# sch.net
KiCad netlist of a schematic drawn in Altium Designer
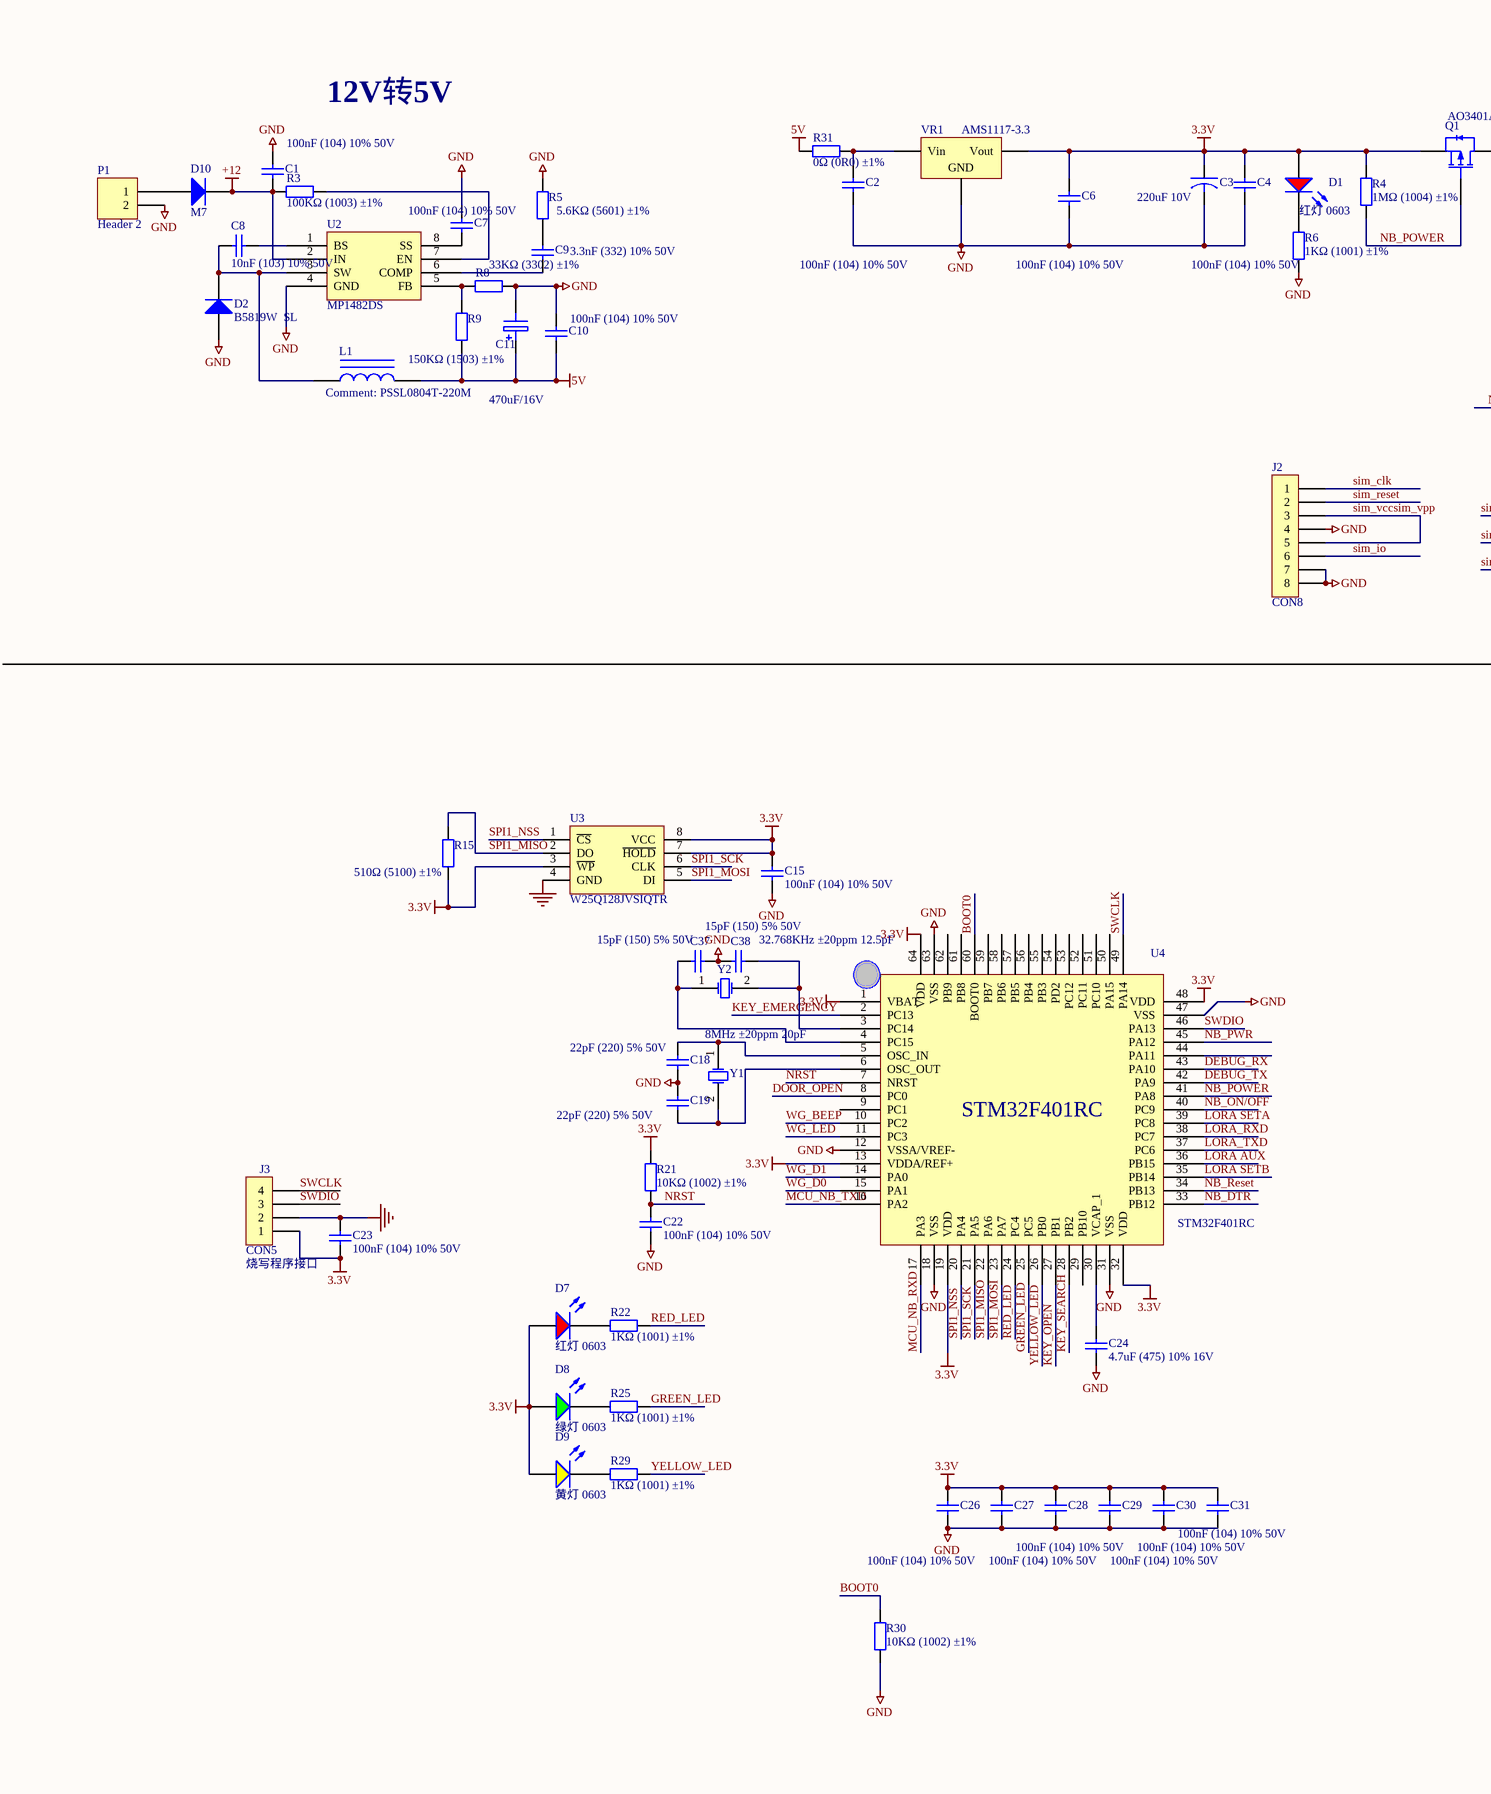
[diagram p0: sch.SchDoc, left]
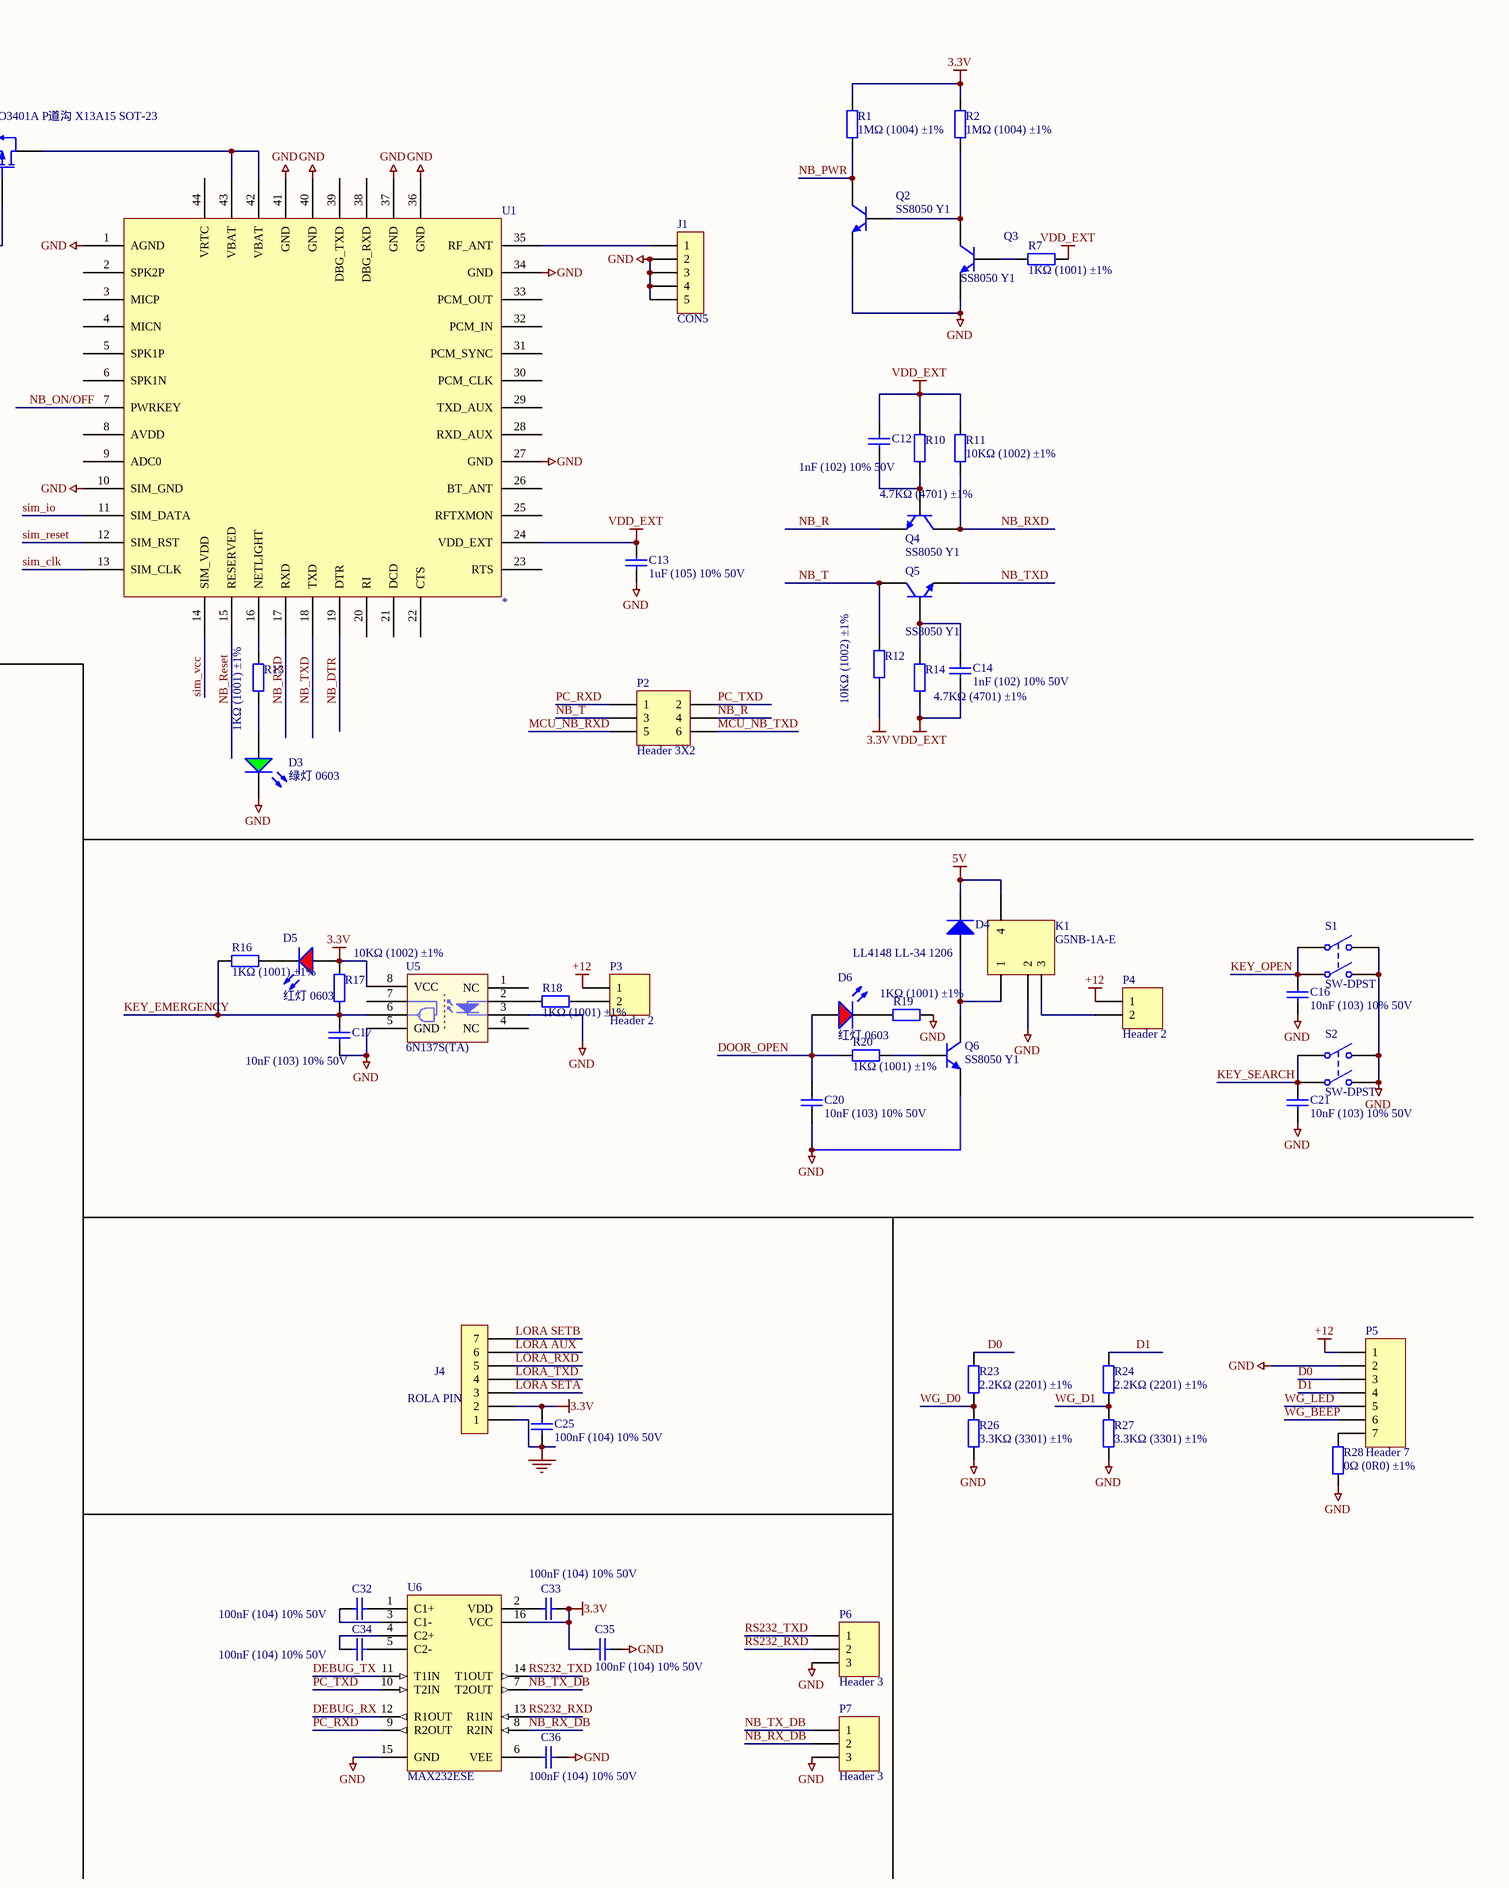
[diagram p1: sch.SchDoc, right]

(export (version "E")
  (design (tool "Eeschema 10.0.6"))
  (components
    (comp (ref "C1")
      (value "100nF (104) 10% 50V")
      (footprint "0603_C")
      (description "贴片电容")
      (libsource (lib "Cap") (part "0603 100nF (104) 10% 50V"))
    )
    (comp (ref "C2")
      (value "100nF (104) 10% 50V")
      (footprint "0603_C")
      (description "贴片电容")
      (libsource (lib "Cap") (part "0603 100nF (104) 10% 50V"))
    )
    (comp (ref "C3")
      (value "220uF 10V")
      (footprint "153CLV-0807")
      (description "Capacitor")
      (libsource (lib "*") (part "CAPACITOR"))
    )
    (comp (ref "C4")
      (value "100nF (104) 10% 50V")
      (footprint "0603_C")
      (description "贴片电容")
      (libsource (lib "Cap") (part "0603 100nF (104) 10% 50V"))
    )
    (comp (ref "C6")
      (value "100nF (104) 10% 50V")
      (footprint "0603_C")
      (description "贴片电容")
      (libsource (lib "Cap") (part "0603 100nF (104) 10% 50V"))
    )
    (comp (ref "C7")
      (value "100nF (104) 10% 50V")
      (footprint "0603_C")
      (description "贴片电容")
      (libsource (lib "Cap") (part "0603 100nF (104) 10% 50V"))
    )
    (comp (ref "C8")
      (value "10nF (103) 10% 50V")
      (footprint "0603_C")
      (description "贴片电容")
      (libsource (lib "Cap") (part "0603 10nF (103) 10% 50V"))
    )
    (comp (ref "C9")
      (value "3.3nF (332) 10% 50V")
      (footprint "0603_C")
      (description "贴片电容")
      (libsource (lib "Cap") (part "0603 3.3nF (332) 10% 50V"))
    )
    (comp (ref "C10")
      (value "100nF (104) 10% 50V")
      (footprint "0603_C")
      (description "贴片电容")
      (libsource (lib "Cap") (part "0603 100nF (104) 10% 50V"))
    )
    (comp (ref "C11")
      (value "470uF/16V")
      (footprint "153CLV-0810")
      (description "Electrolytic Capacitor")
      (libsource (lib "*") (part "ELECTRO1"))
    )
    (comp (ref "C12")
      (value "1nF (102) 10% 50V")
      (footprint "0603_C")
      (description "贴片电容")
      (libsource (lib "Cap") (part "0603 1nF (102) 10% 50V"))
    )
    (comp (ref "C13")
      (value "1uF (105) 10% 50V")
      (footprint "0603_C")
      (description "贴片电容")
      (libsource (lib "Cap") (part "0603 1uF (105) 10% 50V"))
    )
    (comp (ref "C14")
      (value "1nF (102) 10% 50V")
      (footprint "0603_C")
      (description "贴片电容")
      (libsource (lib "Cap") (part "0603 1nF (102) 10% 50V"))
    )
    (comp (ref "C15")
      (value "100nF (104) 10% 50V")
      (footprint "0603_C")
      (description "贴片电容")
      (libsource (lib "Cap") (part "0603 100nF (104) 10% 50V"))
    )
    (comp (ref "C16")
      (value "10nF (103) 10% 50V")
      (footprint "0603_C")
      (description "贴片电容")
      (libsource (lib "Cap") (part "0603 10nF (103) 10% 50V"))
    )
    (comp (ref "C17")
      (value "10nF (103) 10% 50V")
      (footprint "0603_C")
      (description "贴片电容")
      (libsource (lib "Cap") (part "0603 10nF (103) 10% 50V"))
    )
    (comp (ref "C18")
      (value "22pF (220) 5% 50V")
      (footprint "0603_C")
      (description "贴片电容")
      (libsource (lib "Cap") (part "0603 22pF (220) 5% 50V"))
    )
    (comp (ref "C19")
      (value "22pF (220) 5% 50V")
      (footprint "0603_C")
      (description "贴片电容")
      (libsource (lib "Cap") (part "0603 22pF (220) 5% 50V"))
    )
    (comp (ref "C20")
      (value "10nF (103) 10% 50V")
      (footprint "0603_C")
      (description "贴片电容")
      (libsource (lib "Cap") (part "0603 10nF (103) 10% 50V"))
    )
    (comp (ref "C21")
      (value "10nF (103) 10% 50V")
      (footprint "0603_C")
      (description "贴片电容")
      (libsource (lib "Cap") (part "0603 10nF (103) 10% 50V"))
    )
    (comp (ref "C22")
      (value "100nF (104) 10% 50V")
      (footprint "0603_C")
      (description "贴片电容")
      (libsource (lib "Cap") (part "0603 100nF (104) 10% 50V"))
    )
    (comp (ref "C23")
      (value "100nF (104) 10% 50V")
      (footprint "0603_C")
      (description "贴片电容")
      (libsource (lib "Cap") (part "0603 100nF (104) 10% 50V"))
    )
    (comp (ref "C24")
      (value "4.7uF (475) 10% 16V")
      (footprint "0603_C")
      (description "贴片电容")
      (libsource (lib "Cap") (part "0603 4.7uF (475) 10% 16V"))
    )
    (comp (ref "C25")
      (value "100nF (104) 10% 50V")
      (footprint "0603_C")
      (description "贴片电容")
      (libsource (lib "Cap") (part "0603 100nF (104) 10% 50V"))
    )
    (comp (ref "C26")
      (value "100nF (104) 10% 50V")
      (footprint "0603_C")
      (description "贴片电容")
      (libsource (lib "Cap") (part "0603 100nF (104) 10% 50V"))
    )
    (comp (ref "C27")
      (value "100nF (104) 10% 50V")
      (footprint "0603_C")
      (description "贴片电容")
      (libsource (lib "Cap") (part "0603 100nF (104) 10% 50V"))
    )
    (comp (ref "C28")
      (value "100nF (104) 10% 50V")
      (footprint "0603_C")
      (description "贴片电容")
      (libsource (lib "Cap") (part "0603 100nF (104) 10% 50V"))
    )
    (comp (ref "C29")
      (value "100nF (104) 10% 50V")
      (footprint "0603_C")
      (description "贴片电容")
      (libsource (lib "Cap") (part "0603 100nF (104) 10% 50V"))
    )
    (comp (ref "C30")
      (value "100nF (104) 10% 50V")
      (footprint "0603_C")
      (description "贴片电容")
      (libsource (lib "Cap") (part "0603 100nF (104) 10% 50V"))
    )
    (comp (ref "C31")
      (value "100nF (104) 10% 50V")
      (footprint "0603_C")
      (description "贴片电容")
      (libsource (lib "Cap") (part "0603 100nF (104) 10% 50V"))
    )
    (comp (ref "C32")
      (value "100nF (104) 10% 50V")
      (footprint "0603_C")
      (description "贴片电容")
      (libsource (lib "Cap") (part "0603 100nF (104) 10% 50V"))
    )
    (comp (ref "C33")
      (value "100nF (104) 10% 50V")
      (footprint "0603_C")
      (description "贴片电容")
      (libsource (lib "Cap") (part "0603 100nF (104) 10% 50V"))
    )
    (comp (ref "C34")
      (value "100nF (104) 10% 50V")
      (footprint "0603_C")
      (description "贴片电容")
      (libsource (lib "Cap") (part "0603 100nF (104) 10% 50V"))
    )
    (comp (ref "C35")
      (value "100nF (104) 10% 50V")
      (footprint "0603_C")
      (description "贴片电容")
      (libsource (lib "Cap") (part "0603 100nF (104) 10% 50V"))
    )
    (comp (ref "C36")
      (value "100nF (104) 10% 50V")
      (footprint "0603_C")
      (description "贴片电容")
      (libsource (lib "Cap") (part "0603 100nF (104) 10% 50V"))
    )
    (comp (ref "C37")
      (value "15pF (150) 5% 50V")
      (footprint "0603_C")
      (description "贴片电容")
      (libsource (lib "Cap") (part "0603 15pF (150) 5% 50V"))
    )
    (comp (ref "C38")
      (value "15pF (150) 5% 50V")
      (footprint "0603_C")
      (description "贴片电容")
      (libsource (lib "Cap") (part "0603 15pF (150) 5% 50V"))
    )
    (comp (ref "D1")
      (value "红灯 0603")
      (footprint "0603_LED_S1")
      (description "发光二极管")
      (libsource (lib "LED") (part "0603 红灯"))
    )
    (comp (ref "D2")
      (value "B5819W  SL")
      (footprint "SOD-123")
      (description "肖特基二极管")
      (libsource (lib "Diode") (part "SOD-123 B5819W  SL"))
    )
    (comp (ref "D3")
      (value "绿灯 0603")
      (footprint "0603_LED_S1")
      (description "发光二极管")
      (libsource (lib "LED") (part "0603 绿灯"))
    )
    (comp (ref "D4")
      (value "LL4148 LL-34 1206")
      (footprint "LL-34")
      (description "开关二极管")
      (libsource (lib "Diode") (part "LL-34 LL4148 LL-34 1206"))
    )
    (comp (ref "D5")
      (value "红灯 0603")
      (footprint "0603_LED_S1")
      (description "发光二极管")
      (libsource (lib "LED") (part "0603 红灯"))
    )
    (comp (ref "D6")
      (value "红灯 0603")
      (footprint "0603_LED_S1")
      (description "发光二极管")
      (libsource (lib "LED") (part "0603 红灯"))
    )
    (comp (ref "D7")
      (value "红灯 0603")
      (footprint "0603_LED_S1")
      (description "发光二极管")
      (libsource (lib "LED") (part "0603 红灯"))
    )
    (comp (ref "D8")
      (value "绿灯 0603")
      (footprint "0603_LED_S1")
      (description "发光二极管")
      (libsource (lib "LED") (part "0603 绿灯"))
    )
    (comp (ref "D9")
      (value "黄灯 0603")
      (footprint "0603_LED_S1")
      (description "发光二极管")
      (libsource (lib "LED") (part "0603 黄灯"))
    )
    (comp (ref "D10")
      (value "M7")
      (footprint "SMA(DO-214AC)_S1")
      (description "二极管")
      (libsource (lib "Diode") (part "SMA(DO-214AC) M7"))
    )
    (comp (ref "J1")
      (value "CON5")
      (footprint "T-5P")
      (description "Connector")
      (libsource (lib "*") (part "CON5"))
    )
    (comp (ref "J2")
      (value "CON8")
      (footprint "NANOSIM")
      (description "Connector")
      (libsource (lib "*") (part "CON8"))
    )
    (comp (ref "J3")
      (value "CON5")
      (footprint "SIP4")
      (description "Connector")
      (libsource (lib "*") (part "CON4"))
    )
    (comp (ref "J4")
      (value "ROLA PIN")
      (footprint "ROLA MODULE")
      (description "Connector")
      (libsource (lib "*") (part "CON7"))
    )
    (comp (ref "K1") (value "G5NB-1A-E") (footprint "G5NB-1A") (libsource (lib "*") (part "G5NB-1A-E")))
    (comp (ref "L1") (value "PSSL0804T-220M") (footprint "L7-8") (libsource (lib "*") (part "INDUCTOR IRON")))
    (comp (ref "P1")
      (value "Header 2")
      (footprint "MSTBV2")
      (description "Header, 2-Pin")
      (fields (field (name "PUBLISHER") "Altium Limited"))
      (libsource (lib "Miscellaneous Connectors") (part "Header 2"))
    )
    (comp (ref "P2")
      (value "Header 3X2")
      (footprint "HDR2X3")
      (description "Header, 3-Pin, Dual row")
      (fields (field (name "PUBLISHER") "Altium Limited"))
      (libsource (lib "Miscellaneous Connectors") (part "Header 3X2"))
    )
    (comp (ref "P3")
      (value "Header 2")
      (footprint "MSTBV2")
      (description "Header, 2-Pin")
      (fields (field (name "PUBLISHER") "Altium Limited"))
      (libsource (lib "") (part "Header 2_1"))
    )
    (comp (ref "P4")
      (value "Header 2")
      (footprint "MSTBV2")
      (description "Header, 2-Pin")
      (fields (field (name "PUBLISHER") "Altium Limited"))
      (libsource (lib "") (part "Header 2_1"))
    )
    (comp (ref "P5")
      (value "Header 7")
      (footprint "MSTBV7")
      (description "Header, 7-Pin")
      (fields (field (name "PUBLISHER") "Altium Limited"))
      (libsource (lib "Miscellaneous Connectors") (part "Header 7"))
    )
    (comp (ref "P6")
      (value "Header 3")
      (footprint "HDR1X3")
      (description "Header, 3-Pin")
      (fields (field (name "PUBLISHER") "Altium Limited"))
      (libsource (lib "Miscellaneous Connectors") (part "Header 3"))
    )
    (comp (ref "P7")
      (value "Header 3")
      (footprint "HDR1X3")
      (description "Header, 3-Pin")
      (fields (field (name "PUBLISHER") "Altium Limited"))
      (libsource (lib "Miscellaneous Connectors") (part "Header 3"))
    )
    (comp (ref "Q1")
      (value "AO3401A P道沟 X13A15 SOT-23")
      (footprint "SOT-23-3L")
      (description "MOS(场效应管)")
      (libsource (lib "MOS") (part "AO3401A P道沟 X13A15 SOT-23"))
    )
    (comp (ref "Q2")
      (value "SS8050 Y1")
      (footprint "SOT-23(SOT-23-3)")
      (description "三极管")
      (libsource (lib "Transistor_NPN") (part "SOT-23 SS8050 Y1"))
    )
    (comp (ref "Q3")
      (value "SS8050 Y1")
      (footprint "SOT-23(SOT-23-3)")
      (description "三极管")
      (libsource (lib "Transistor_NPN") (part "SOT-23 SS8050 Y1"))
    )
    (comp (ref "Q4")
      (value "SS8050 Y1")
      (footprint "SOT-23(SOT-23-3)")
      (description "三极管")
      (libsource (lib "Transistor_NPN") (part "SOT-23 SS8050 Y1"))
    )
    (comp (ref "Q5")
      (value "SS8050 Y1")
      (footprint "SOT-23(SOT-23-3)")
      (description "三极管")
      (libsource (lib "Transistor_NPN") (part "SOT-23 SS8050 Y1"))
    )
    (comp (ref "Q6")
      (value "SS8050 Y1")
      (footprint "SOT-23(SOT-23-3)")
      (description "三极管")
      (libsource (lib "Transistor_NPN") (part "SOT-23 SS8050 Y1"))
    )
    (comp (ref "R1")
      (value "1MΩ (1004) ±1%")
      (footprint "0603_R")
      (description "贴片电阻")
      (libsource (lib "RES") (part "0603 1MΩ (1004) 1%"))
    )
    (comp (ref "R2")
      (value "1MΩ (1004) ±1%")
      (footprint "0603_R")
      (description "贴片电阻")
      (libsource (lib "RES") (part "0603 1MΩ (1004) 1%"))
    )
    (comp (ref "R3")
      (value "100KΩ (1003) ±1%")
      (footprint "0603_R")
      (description "贴片电阻")
      (libsource (lib "RES") (part "0603 100KΩ (1003) 1%"))
    )
    (comp (ref "R4")
      (value "1MΩ (1004) ±1%")
      (footprint "0603_R")
      (description "贴片电阻")
      (libsource (lib "RES") (part "0603 1MΩ (1004) 1%"))
    )
    (comp (ref "R5")
      (value "5.6KΩ (5601) ±1%")
      (footprint "0603_R")
      (description "贴片电阻")
      (libsource (lib "RES") (part "0603 5.6KΩ (5601) 1%"))
    )
    (comp (ref "R6")
      (value "1KΩ (1001) ±1%")
      (footprint "0603_R")
      (description "贴片电阻")
      (libsource (lib "RES") (part "0603 1KΩ (1001) 1%"))
    )
    (comp (ref "R7")
      (value "1KΩ (1001) ±1%")
      (footprint "0603_R")
      (description "贴片电阻")
      (libsource (lib "") (part "0603 1KΩ (1001) 1%_1"))
    )
    (comp (ref "R8")
      (value "33KΩ (3302) ±1%")
      (footprint "0603_R")
      (description "贴片电阻")
      (libsource (lib "RES") (part "0603 33KΩ (3302) 1%"))
    )
    (comp (ref "R9")
      (value "150KΩ (1503) ±1%")
      (footprint "0603_R")
      (description "贴片电阻")
      (libsource (lib "RES") (part "0603 150KΩ (1503) 1%"))
    )
    (comp (ref "R10")
      (value "4.7KΩ (4701) ±1%")
      (footprint "0603_R")
      (description "贴片电阻")
      (libsource (lib "RES") (part "0603 4.7KΩ (4701) 1%"))
    )
    (comp (ref "R11")
      (value "10KΩ (1002) ±1%")
      (footprint "0603_R")
      (description "贴片电阻")
      (libsource (lib "RES") (part "0603 10KΩ (1002) 1%"))
    )
    (comp (ref "R12")
      (value "10KΩ (1002) ±1%")
      (footprint "0603_R")
      (description "贴片电阻")
      (libsource (lib "RES") (part "0603 10KΩ (1002) 1%"))
    )
    (comp (ref "R13")
      (value "1KΩ (1001) ±1%")
      (footprint "0603_R")
      (description "贴片电阻")
      (libsource (lib "RES") (part "0603 1KΩ (1001) 1%"))
    )
    (comp (ref "R14")
      (value "4.7KΩ (4701) ±1%")
      (footprint "0603_R")
      (description "贴片电阻")
      (libsource (lib "RES") (part "0603 4.7KΩ (4701) 1%"))
    )
    (comp (ref "R15")
      (value "510Ω (5100) ±1%")
      (footprint "0603_R")
      (description "贴片电阻")
      (libsource (lib "RES") (part "0603 510Ω (5100) 1%"))
    )
    (comp (ref "R16")
      (value "1KΩ (1001) ±1%")
      (footprint "0603_R")
      (description "贴片电阻")
      (libsource (lib "") (part "0603 1KΩ (1001) 1%_1"))
    )
    (comp (ref "R17")
      (value "10KΩ (1002) ±1%")
      (footprint "0603_R")
      (description "贴片电阻")
      (libsource (lib "") (part "0603 10KΩ (1002) 1%_1"))
    )
    (comp (ref "R18")
      (value "1KΩ (1001) ±1%")
      (footprint "1206_R")
      (description "贴片电阻")
      (libsource (lib "RES") (part "1206 1KΩ (1001) 1%"))
    )
    (comp (ref "R19")
      (value "1KΩ (1001) ±1%")
      (footprint "0603_R")
      (description "贴片电阻")
      (libsource (lib "") (part "0603 1KΩ (1001) 1%_2"))
    )
    (comp (ref "R20")
      (value "1KΩ (1001) ±1%")
      (footprint "0603_R")
      (description "贴片电阻")
      (libsource (lib "") (part "0603 1KΩ (1001) 1%_1"))
    )
    (comp (ref "R21")
      (value "10KΩ (1002) ±1%")
      (footprint "0603_R")
      (description "贴片电阻")
      (libsource (lib "RES") (part "0603 10KΩ (1002) 1%"))
    )
    (comp (ref "R22")
      (value "1KΩ (1001) ±1%")
      (footprint "0603_R")
      (description "贴片电阻")
      (libsource (lib "") (part "0603 1KΩ (1001) 1%_1"))
    )
    (comp (ref "R23")
      (value "2.2KΩ (2201) ±1%")
      (footprint "0603_R")
      (description "贴片电阻")
      (libsource (lib "RES") (part "0603 2.2KΩ (2201) 1%"))
    )
    (comp (ref "R24")
      (value "2.2KΩ (2201) ±1%")
      (footprint "0603_R")
      (description "贴片电阻")
      (libsource (lib "RES") (part "0603 2.2KΩ (2201) 1%"))
    )
    (comp (ref "R25")
      (value "1KΩ (1001) ±1%")
      (footprint "0603_R")
      (description "贴片电阻")
      (libsource (lib "") (part "0603 1KΩ (1001) 1%_1"))
    )
    (comp (ref "R26")
      (value "3.3KΩ (3301) ±1%")
      (footprint "0603_R")
      (description "贴片电阻")
      (libsource (lib "RES") (part "0603 3.3KΩ (3301) 1%"))
    )
    (comp (ref "R27")
      (value "3.3KΩ (3301) ±1%")
      (footprint "0603_R")
      (description "贴片电阻")
      (libsource (lib "RES") (part "0603 3.3KΩ (3301) 1%"))
    )
    (comp (ref "R28")
      (value "0Ω (0R0) ±1%")
      (footprint "0603_R")
      (description "贴片电阻")
      (libsource (lib "RES") (part "0603 0Ω (0R0) 1%"))
    )
    (comp (ref "R29")
      (value "1KΩ (1001) ±1%")
      (footprint "0603_R")
      (description "贴片电阻")
      (libsource (lib "") (part "0603 1KΩ (1001) 1%_1"))
    )
    (comp (ref "R30")
      (value "10KΩ (1002) ±1%")
      (footprint "0603_R")
      (description "贴片电阻")
      (libsource (lib "") (part "0603 10KΩ (1002) 1%_1"))
    )
    (comp (ref "R31")
      (value "0Ω (0R0) ±1%")
      (footprint "0805_R")
      (description "贴片电阻")
      (libsource (lib "RES") (part "0805 0Ω (0R0) 1%"))
    )
    (comp (ref "S1")
      (value "SW-DPST")
      (footprint "12*12_key")
      (description "Double-Pole, Single-Throw Switch")
      (fields (field (name "PUBLISHER") "Altium Limited"))
      (libsource (lib "Miscellaneous Devices") (part "SW-DPST"))
    )
    (comp (ref "S2")
      (value "SW-DPST")
      (footprint "12*12_key")
      (description "Double-Pole, Single-Throw Switch")
      (fields (field (name "PUBLISHER") "Altium Limited"))
      (libsource (lib "Miscellaneous Devices") (part "SW-DPST"))
    )
    (comp (ref "U1") (value "*") (footprint "M26") (libsource (lib "*") (part "M26")))
    (comp (ref "U2")
      (value "MP1482DS")
      (footprint "SOIC-8_150mil")
      (description "电源芯片")
      (libsource (lib "IC") (part "MP1482DS_[C14867]"))
    )
    (comp (ref "U3")
      (value "W25Q128JVSIQTR")
      (footprint "SOIC-8_208mil")
      (description "Flash ROM")
      (libsource (lib "IC") (part "W25Q128JVSIQTR_[C97521]"))
    )
    (comp (ref "U4") (value "STM32F401RC") (footprint "LQFP64") (libsource (lib "*") (part "STM32F401RC")))
    (comp (ref "U5")
      (value "6N137S(TA)")
      (footprint "SMD-8_6.3mm")
      (description "贴片光耦")
      (libsource (lib "IC") (part "6N137S(TA)_[C16496]"))
    )
    (comp (ref "U6")
      (value "MAX232ESE")
      (footprint "SOIC-16_150mil")
      (description "RS232")
      (libsource (lib "IC") (part "MAX232ESE_[C26860]"))
    )
    (comp (ref "VR1")
      (value "AMS1117-3.3")
      (footprint "SOT-223")
      (description "低压差线性稳压(LDO)")
      (libsource (lib "LDO") (part "SOT-223 AMS1117-3.3"))
    )
    (comp (ref "Y1")
      (value "8MHz ±20ppm 20pF")
      (footprint "SMD-5032_2P")
      (description "贴片晶振")
      (libsource (lib "CrystalOscillator") (part "SMD-5032_2P 8MHz 20ppm 20pF"))
    )
    (comp (ref "Y2")
      (value "32.768KHz ±20ppm 12.5pF")
      (footprint "SMD-3215_2P FC - 135")
      (description "贴片晶振")
      (libsource (lib "CrystalOscillator") (part "SMD-3215_2P 32.768KHz 20ppm 12.5pF"))
    )
  )
  (nets
    (net (code "1") (name "+12") (class "Default")
      (node (ref "C1") (pin "2") (pinfunction "2_2") (pintype "passive"))
      (node (ref "D10") (pin "2") (pinfunction "K_2") (pintype "passive"))
      (node (ref "P3") (pin "1") (pinfunction "1_1") (pintype "passive"))
      (node (ref "P4") (pin "1") (pinfunction "1_1") (pintype "passive"))
      (node (ref "P5") (pin "1") (pinfunction "1_1") (pintype "passive"))
      (node (ref "R3") (pin "1") (pinfunction "1_1") (pintype "passive"))
      (node (ref "U2") (pin "2") (pinfunction "IN_2") (pintype "passive"))
    )
    (net (code "2") (name "/BOOT0") (class "Default")
      (node (ref "R30") (pin "1") (pinfunction "1_1") (pintype "passive"))
      (node (ref "U4") (pin "60") (pinfunction "BOOT0_60") (pintype "passive"))
    )
    (net (code "3") (name "/D0") (class "Default")
      (node (ref "P5") (pin "3") (pinfunction "3_3") (pintype "passive"))
      (node (ref "R23") (pin "2") (pinfunction "2_2") (pintype "passive"))
    )
    (net (code "4") (name "/D1") (class "Default")
      (node (ref "P5") (pin "4") (pinfunction "4_4") (pintype "passive"))
      (node (ref "R24") (pin "2") (pinfunction "2_2") (pintype "passive"))
    )
    (net (code "5") (name "/DEBUG_RX") (class "Default")
      (node (ref "U4") (pin "43") (pinfunction "PA10_43") (pintype "passive"))
      (node (ref "U6") (pin "12") (pinfunction "R1OUT_12") (pintype "output"))
    )
    (net (code "6") (name "/DEBUG_TX") (class "Default")
      (node (ref "U4") (pin "42") (pinfunction "PA9_42") (pintype "passive"))
      (node (ref "U6") (pin "11") (pinfunction "T1IN_11") (pintype "input"))
    )
    (net (code "7") (name "/DOOR_OPEN") (class "Default")
      (node (ref "C20") (pin "1") (pinfunction "1_1") (pintype "passive"))
      (node (ref "D6") (pin "A") (pinfunction "A_A") (pintype "passive"))
      (node (ref "R20") (pin "1") (pinfunction "1_1") (pintype "passive"))
      (node (ref "U4") (pin "8") (pinfunction "PC0_8") (pintype "passive"))
    )
    (net (code "8") (name "/GREEN_LED") (class "Default")
      (node (ref "R25") (pin "2") (pinfunction "2_2") (pintype "passive"))
      (node (ref "U4") (pin "25") (pinfunction "PC5_25") (pintype "passive"))
    )
    (net (code "9") (name "/KEY_EMERGENCY") (class "Default")
      (node (ref "C17") (pin "2") (pinfunction "2_2") (pintype "passive"))
      (node (ref "R16") (pin "1") (pinfunction "1_1") (pintype "passive"))
      (node (ref "R17") (pin "2") (pinfunction "2_2") (pintype "passive"))
      (node (ref "U4") (pin "2") (pinfunction "PC13_2") (pintype "passive"))
      (node (ref "U5") (pin "6") (pinfunction "VO_6") (pintype "passive"))
    )
    (net (code "10") (name "/KEY_OPEN") (class "Default")
      (node (ref "C16") (pin "1") (pinfunction "1_1") (pintype "passive"))
      (node (ref "S1") (pin "1") (pinfunction "COMMON1_1") (pintype "passive"))
      (node (ref "S1") (pin "3") (pinfunction "COMMON2_3") (pintype "passive"))
      (node (ref "U4") (pin "27") (pinfunction "PB1_27") (pintype "passive"))
    )
    (net (code "11") (name "/KEY_SEARCH") (class "Default")
      (node (ref "C21") (pin "1") (pinfunction "1_1") (pintype "passive"))
      (node (ref "S2") (pin "1") (pinfunction "COMMON1_1") (pintype "passive"))
      (node (ref "S2") (pin "3") (pinfunction "COMMON2_3") (pintype "passive"))
      (node (ref "U4") (pin "28") (pinfunction "PB2_28") (pintype "passive"))
    )
    (net (code "12") (name "/LORA AUX") (class "Default")
      (node (ref "J4") (pin "6") (pinfunction "6_6") (pintype "passive"))
      (node (ref "U4") (pin "36") (pinfunction "PB15_36") (pintype "passive"))
    )
    (net (code "13") (name "/LORA SETA") (class "Default")
      (node (ref "J4") (pin "3") (pinfunction "3_3") (pintype "passive"))
      (node (ref "U4") (pin "39") (pinfunction "PC8_39") (pintype "passive"))
    )
    (net (code "14") (name "/LORA SETB") (class "Default")
      (node (ref "J4") (pin "7") (pinfunction "7_7") (pintype "passive"))
      (node (ref "U4") (pin "35") (pinfunction "PB14_35") (pintype "passive"))
    )
    (net (code "15") (name "/LORA_RXD") (class "Default")
      (node (ref "J4") (pin "5") (pinfunction "5_5") (pintype "passive"))
      (node (ref "U4") (pin "38") (pinfunction "PC7_38") (pintype "passive"))
    )
    (net (code "16") (name "/LORA_TXD") (class "Default")
      (node (ref "J4") (pin "4") (pinfunction "4_4") (pintype "passive"))
      (node (ref "U4") (pin "37") (pinfunction "PC6_37") (pintype "passive"))
    )
    (net (code "17") (name "/MCU_NB_RXD") (class "Default")
      (node (ref "P2") (pin "5") (pinfunction "5_5") (pintype "passive"))
      (node (ref "U4") (pin "17") (pinfunction "PA3_17") (pintype "passive"))
    )
    (net (code "18") (name "/MCU_NB_TXD") (class "Default")
      (node (ref "P2") (pin "6") (pinfunction "6_6") (pintype "passive"))
      (node (ref "U4") (pin "16") (pinfunction "PA2_16") (pintype "passive"))
    )
    (net (code "19") (name "/NB_DTR") (class "Default")
      (node (ref "U1") (pin "19") (pinfunction "DTR_19") (pintype "passive"))
      (node (ref "U4") (pin "33") (pinfunction "PB12_33") (pintype "passive"))
    )
    (net (code "20") (name "/NB_ON{slash}OFF") (class "Default")
      (node (ref "U1") (pin "7") (pinfunction "PWRKEY_7") (pintype "passive"))
      (node (ref "U4") (pin "40") (pinfunction "PC9_40") (pintype "passive"))
    )
    (net (code "21") (name "/NB_POWER") (class "Default")
      (node (ref "Q1") (pin "1") (pinfunction "G_1") (pintype "passive"))
      (node (ref "R4") (pin "1") (pinfunction "1_1") (pintype "passive"))
      (node (ref "U4") (pin "41") (pinfunction "PA8_41") (pintype "passive"))
    )
    (net (code "22") (name "/NB_PWR") (class "Default")
      (node (ref "Q2") (pin "3") (pinfunction "C_3") (pintype "passive"))
      (node (ref "R1") (pin "1") (pinfunction "1_1") (pintype "passive"))
      (node (ref "U4") (pin "45") (pinfunction "PA12_45") (pintype "passive"))
    )
    (net (code "23") (name "/NB_R") (class "Default")
      (node (ref "P2") (pin "4") (pinfunction "4_4") (pintype "passive"))
      (node (ref "Q4") (pin "2") (pinfunction "E_2") (pintype "passive"))
    )
    (net (code "24") (name "/NB_RXD") (class "Default")
      (node (ref "Q4") (pin "3") (pinfunction "C_3") (pintype "passive"))
      (node (ref "R11") (pin "1") (pinfunction "1_1") (pintype "passive"))
      (node (ref "U1") (pin "17") (pinfunction "RXD_17") (pintype "passive"))
    )
    (net (code "25") (name "/NB_RX_DB") (class "Default")
      (node (ref "P7") (pin "2") (pinfunction "2_2") (pintype "passive"))
      (node (ref "U6") (pin "8") (pinfunction "R2IN_8") (pintype "input"))
    )
    (net (code "26") (name "/NB_Reset") (class "Default")
      (node (ref "U1") (pin "15") (pinfunction "RESERVED_15") (pintype "passive"))
      (node (ref "U4") (pin "34") (pinfunction "PB13_34") (pintype "passive"))
    )
    (net (code "27") (name "/NB_T") (class "Default")
      (node (ref "P2") (pin "3") (pinfunction "3_3") (pintype "passive"))
      (node (ref "Q5") (pin "3") (pinfunction "C_3") (pintype "passive"))
      (node (ref "R12") (pin "2") (pinfunction "2_2") (pintype "passive"))
    )
    (net (code "28") (name "/NB_TXD") (class "Default")
      (node (ref "Q5") (pin "2") (pinfunction "E_2") (pintype "passive"))
      (node (ref "U1") (pin "18") (pinfunction "TXD_18") (pintype "passive"))
    )
    (net (code "29") (name "/NB_TX_DB") (class "Default")
      (node (ref "P7") (pin "1") (pinfunction "1_1") (pintype "passive"))
      (node (ref "U6") (pin "7") (pinfunction "T2OUT_7") (pintype "output"))
    )
    (net (code "30") (name "/NRST") (class "Default")
      (node (ref "C22") (pin "1") (pinfunction "1_1") (pintype "passive"))
      (node (ref "R21") (pin "1") (pinfunction "1_1") (pintype "passive"))
      (node (ref "U4") (pin "7") (pinfunction "NRST_7") (pintype "passive"))
    )
    (net (code "31") (name "/PC_RXD") (class "Default")
      (node (ref "P2") (pin "1") (pinfunction "1_1") (pintype "passive"))
      (node (ref "U6") (pin "9") (pinfunction "R2OUT_9") (pintype "output"))
    )
    (net (code "32") (name "/PC_TXD") (class "Default")
      (node (ref "P2") (pin "2") (pinfunction "2_2") (pintype "passive"))
      (node (ref "U6") (pin "10") (pinfunction "T2IN_10") (pintype "input"))
    )
    (net (code "33") (name "/RED_LED") (class "Default")
      (node (ref "R22") (pin "2") (pinfunction "2_2") (pintype "passive"))
      (node (ref "U4") (pin "24") (pinfunction "PC4_24") (pintype "passive"))
    )
    (net (code "34") (name "/RS232_RXD") (class "Default")
      (node (ref "P6") (pin "2") (pinfunction "2_2") (pintype "passive"))
      (node (ref "U6") (pin "13") (pinfunction "R1IN_13") (pintype "input"))
    )
    (net (code "35") (name "/RS232_TXD") (class "Default")
      (node (ref "P6") (pin "1") (pinfunction "1_1") (pintype "passive"))
      (node (ref "U6") (pin "14") (pinfunction "T1OUT_14") (pintype "output"))
    )
    (net (code "36") (name "/SPI1_MISO") (class "Default")
      (node (ref "R15") (pin "2") (pinfunction "2_2") (pintype "passive"))
      (node (ref "U3") (pin "2") (pinfunction "DO_2") (pintype "passive"))
      (node (ref "U4") (pin "22") (pinfunction "PA6_22") (pintype "passive"))
    )
    (net (code "37") (name "/SPI1_MOSI") (class "Default")
      (node (ref "U3") (pin "5") (pinfunction "DI_5") (pintype "passive"))
      (node (ref "U4") (pin "23") (pinfunction "PA7_23") (pintype "passive"))
    )
    (net (code "38") (name "/SPI1_NSS") (class "Default")
      (node (ref "U3") (pin "1") (pinfunction "~{CS}_1") (pintype "passive"))
      (node (ref "U4") (pin "20") (pinfunction "PA4_20") (pintype "passive"))
    )
    (net (code "39") (name "/SPI1_SCK") (class "Default")
      (node (ref "U3") (pin "6") (pinfunction "CLK_6") (pintype "passive"))
      (node (ref "U4") (pin "21") (pinfunction "PA5_21") (pintype "passive"))
    )
    (net (code "40") (name "/SWCLK") (class "Default")
      (node (ref "J3") (pin "4") (pinfunction "4_4") (pintype "passive"))
      (node (ref "U4") (pin "49") (pinfunction "PA14_49") (pintype "passive"))
    )
    (net (code "41") (name "/SWDIO") (class "Default")
      (node (ref "J3") (pin "3") (pinfunction "3_3") (pintype "passive"))
      (node (ref "U4") (pin "46") (pinfunction "PA13_46") (pintype "passive"))
    )
    (net (code "42") (name "/WG_BEEP") (class "Default")
      (node (ref "P5") (pin "6") (pinfunction "6_6") (pintype "passive"))
      (node (ref "U4") (pin "10") (pinfunction "PC2_10") (pintype "passive"))
    )
    (net (code "43") (name "/WG_D0") (class "Default")
      (node (ref "R23") (pin "1") (pinfunction "1_1") (pintype "passive"))
      (node (ref "R26") (pin "2") (pinfunction "2_2") (pintype "passive"))
      (node (ref "U4") (pin "15") (pinfunction "PA1_15") (pintype "passive"))
    )
    (net (code "44") (name "/WG_D1") (class "Default")
      (node (ref "R24") (pin "1") (pinfunction "1_1") (pintype "passive"))
      (node (ref "R27") (pin "2") (pinfunction "2_2") (pintype "passive"))
      (node (ref "U4") (pin "14") (pinfunction "PA0_14") (pintype "passive"))
    )
    (net (code "45") (name "/WG_LED") (class "Default")
      (node (ref "P5") (pin "5") (pinfunction "5_5") (pintype "passive"))
      (node (ref "U4") (pin "11") (pinfunction "PC3_11") (pintype "passive"))
    )
    (net (code "46") (name "/YELLOW_LED") (class "Default")
      (node (ref "R29") (pin "2") (pinfunction "2_2") (pintype "passive"))
      (node (ref "U4") (pin "26") (pinfunction "PB0_26") (pintype "passive"))
    )
    (net (code "47") (name "/sim_clk") (class "Default")
      (node (ref "J2") (pin "1") (pinfunction "1_1") (pintype "passive"))
      (node (ref "U1") (pin "13") (pinfunction "SIM_CLK_13") (pintype "passive"))
    )
    (net (code "48") (name "/sim_io") (class "Default")
      (node (ref "J2") (pin "6") (pinfunction "6_6") (pintype "passive"))
      (node (ref "U1") (pin "11") (pinfunction "SIM_DATA_11") (pintype "passive"))
    )
    (net (code "49") (name "/sim_reset") (class "Default")
      (node (ref "J2") (pin "2") (pinfunction "2_2") (pintype "passive"))
      (node (ref "U1") (pin "12") (pinfunction "SIM_RST_12") (pintype "passive"))
    )
    (net (code "50") (name "/sim_vcc") (class "Default")
      (node (ref "J2") (pin "3") (pinfunction "3_3") (pintype "passive"))
      (node (ref "J2") (pin "5") (pinfunction "5_5") (pintype "passive"))
      (node (ref "U1") (pin "14") (pinfunction "SIM_VDD_14") (pintype "passive"))
    )
    (net (code "51") (name "3.3V") (class "Default")
      (node (ref "C15") (pin "1") (pinfunction "1_1") (pintype "passive"))
      (node (ref "C23") (pin "1") (pinfunction "1_1") (pintype "passive"))
      (node (ref "C25") (pin "1") (pinfunction "1_1") (pintype "passive"))
      (node (ref "C26") (pin "2") (pinfunction "2_2") (pintype "passive"))
      (node (ref "C27") (pin "2") (pinfunction "2_2") (pintype "passive"))
      (node (ref "C28") (pin "2") (pinfunction "2_2") (pintype "passive"))
      (node (ref "C29") (pin "2") (pinfunction "2_2") (pintype "passive"))
      (node (ref "C3") (pin "1") (pinfunction "1_1") (pintype "passive"))
      (node (ref "C30") (pin "2") (pinfunction "2_2") (pintype "passive"))
      (node (ref "C31") (pin "2") (pinfunction "2_2") (pintype "passive"))
      (node (ref "C33") (pin "2") (pinfunction "2_2") (pintype "passive"))
      (node (ref "C35") (pin "2") (pinfunction "2_2") (pintype "passive"))
      (node (ref "C4") (pin "2") (pinfunction "2_2") (pintype "passive"))
      (node (ref "C6") (pin "2") (pinfunction "2_2") (pintype "passive"))
      (node (ref "D1") (pin "A") (pinfunction "A_A") (pintype "passive"))
      (node (ref "D5") (pin "A") (pinfunction "A_A") (pintype "passive"))
      (node (ref "D7") (pin "A") (pinfunction "A_A") (pintype "passive"))
      (node (ref "D8") (pin "A") (pinfunction "A_A") (pintype "passive"))
      (node (ref "D9") (pin "A") (pinfunction "A_A") (pintype "passive"))
      (node (ref "J3") (pin "1") (pinfunction "1_1") (pintype "passive"))
      (node (ref "J4") (pin "2") (pinfunction "2_2") (pintype "passive"))
      (node (ref "Q1") (pin "2") (pinfunction "S_2") (pintype "passive"))
      (node (ref "R1") (pin "2") (pinfunction "2_2") (pintype "passive"))
      (node (ref "R12") (pin "1") (pinfunction "1_1") (pintype "passive"))
      (node (ref "R15") (pin "1") (pinfunction "1_1") (pintype "passive"))
      (node (ref "R17") (pin "1") (pinfunction "1_1") (pintype "passive"))
      (node (ref "R2") (pin "2") (pinfunction "2_2") (pintype "passive"))
      (node (ref "R21") (pin "2") (pinfunction "2_2") (pintype "passive"))
      (node (ref "R4") (pin "2") (pinfunction "2_2") (pintype "passive"))
      (node (ref "U3") (pin "3") (pinfunction "~{WP}_3") (pintype "passive"))
      (node (ref "U3") (pin "7") (pinfunction "~{HOLD}_7") (pintype "passive"))
      (node (ref "U3") (pin "8") (pinfunction "VCC_8") (pintype "passive"))
      (node (ref "U4") (pin "1") (pinfunction "VBAT_1") (pintype "passive"))
      (node (ref "U4") (pin "13") (pinfunction "VDDA/REF+_13") (pintype "passive"))
      (node (ref "U4") (pin "19") (pinfunction "VDD_19") (pintype "passive"))
      (node (ref "U4") (pin "32") (pinfunction "VDD_32") (pintype "passive"))
      (node (ref "U4") (pin "48") (pinfunction "VDD_48") (pintype "passive"))
      (node (ref "U4") (pin "64") (pinfunction "VDD_64") (pintype "passive"))
      (node (ref "U5") (pin "8") (pinfunction "VCC_8") (pintype "passive"))
      (node (ref "U6") (pin "16") (pinfunction "VCC_16") (pintype "power_in"))
      (node (ref "VR1") (pin "2") (pinfunction "Vout_2") (pintype "passive"))
    )
    (net (code "52") (name "5V") (class "Default")
      (node (ref "C10") (pin "1") (pinfunction "1_1") (pintype "passive"))
      (node (ref "C11") (pin "1") (pinfunction "1_1") (pintype "passive"))
      (node (ref "D4") (pin "2") (pinfunction "K_2") (pintype "passive"))
      (node (ref "K1") (pin "4") (pinfunction "4_4") (pintype "passive"))
      (node (ref "L1") (pin "2") (pinfunction "2_2") (pintype "passive"))
      (node (ref "R31") (pin "1") (pinfunction "1_1") (pintype "passive"))
      (node (ref "R9") (pin "2") (pinfunction "2_2") (pintype "passive"))
    )
    (net (code "53") (name "GND") (class "Default")
      (node (ref "C1") (pin "1") (pinfunction "1_1") (pintype "passive"))
      (node (ref "C10") (pin "2") (pinfunction "2_2") (pintype "passive"))
      (node (ref "C11") (pin "2") (pinfunction "2_2") (pintype "passive"))
      (node (ref "C13") (pin "1") (pinfunction "1_1") (pintype "passive"))
      (node (ref "C15") (pin "2") (pinfunction "2_2") (pintype "passive"))
      (node (ref "C16") (pin "2") (pinfunction "2_2") (pintype "passive"))
      (node (ref "C17") (pin "1") (pinfunction "1_1") (pintype "passive"))
      (node (ref "C18") (pin "1") (pinfunction "1_1") (pintype "passive"))
      (node (ref "C19") (pin "2") (pinfunction "2_2") (pintype "passive"))
      (node (ref "C2") (pin "1") (pinfunction "1_1") (pintype "passive"))
      (node (ref "C20") (pin "2") (pinfunction "2_2") (pintype "passive"))
      (node (ref "C21") (pin "2") (pinfunction "2_2") (pintype "passive"))
      (node (ref "C22") (pin "2") (pinfunction "2_2") (pintype "passive"))
      (node (ref "C23") (pin "2") (pinfunction "2_2") (pintype "passive"))
      (node (ref "C24") (pin "2") (pinfunction "2_2") (pintype "passive"))
      (node (ref "C25") (pin "2") (pinfunction "2_2") (pintype "passive"))
      (node (ref "C26") (pin "1") (pinfunction "1_1") (pintype "passive"))
      (node (ref "C27") (pin "1") (pinfunction "1_1") (pintype "passive"))
      (node (ref "C28") (pin "1") (pinfunction "1_1") (pintype "passive"))
      (node (ref "C29") (pin "1") (pinfunction "1_1") (pintype "passive"))
      (node (ref "C3") (pin "2") (pinfunction "2_2") (pintype "passive"))
      (node (ref "C30") (pin "1") (pinfunction "1_1") (pintype "passive"))
      (node (ref "C31") (pin "1") (pinfunction "1_1") (pintype "passive"))
      (node (ref "C35") (pin "1") (pinfunction "1_1") (pintype "passive"))
      (node (ref "C36") (pin "2") (pinfunction "2_2") (pintype "passive"))
      (node (ref "C37") (pin "2") (pinfunction "2_2") (pintype "passive"))
      (node (ref "C38") (pin "1") (pinfunction "1_1") (pintype "passive"))
      (node (ref "C4") (pin "1") (pinfunction "1_1") (pintype "passive"))
      (node (ref "C6") (pin "1") (pinfunction "1_1") (pintype "passive"))
      (node (ref "C7") (pin "1") (pinfunction "1_1") (pintype "passive"))
      (node (ref "D2") (pin "1") (pinfunction "A_1") (pintype "passive"))
      (node (ref "D3") (pin "K") (pinfunction "K_K") (pintype "passive"))
      (node (ref "J1") (pin "2") (pinfunction "2_2") (pintype "passive"))
      (node (ref "J1") (pin "3") (pinfunction "3_3") (pintype "passive"))
      (node (ref "J1") (pin "4") (pinfunction "4_4") (pintype "passive"))
      (node (ref "J1") (pin "5") (pinfunction "5_5") (pintype "passive"))
      (node (ref "J2") (pin "4") (pinfunction "4_4") (pintype "passive"))
      (node (ref "J2") (pin "7") (pinfunction "7_7") (pintype "passive"))
      (node (ref "J2") (pin "8") (pinfunction "8_8") (pintype "passive"))
      (node (ref "J3") (pin "2") (pinfunction "2_2") (pintype "passive"))
      (node (ref "J4") (pin "1") (pinfunction "1_1") (pintype "passive"))
      (node (ref "K1") (pin "2") (pinfunction "2_2") (pintype "passive"))
      (node (ref "P1") (pin "2") (pinfunction "2_2") (pintype "passive"))
      (node (ref "P5") (pin "2") (pinfunction "2_2") (pintype "passive"))
      (node (ref "P6") (pin "3") (pinfunction "3_3") (pintype "passive"))
      (node (ref "P7") (pin "3") (pinfunction "3_3") (pintype "passive"))
      (node (ref "Q2") (pin "2") (pinfunction "E_2") (pintype "passive"))
      (node (ref "Q3") (pin "2") (pinfunction "E_2") (pintype "passive"))
      (node (ref "Q6") (pin "2") (pinfunction "E_2") (pintype "passive"))
      (node (ref "R19") (pin "1") (pinfunction "1_1") (pintype "passive"))
      (node (ref "R26") (pin "1") (pinfunction "1_1") (pintype "passive"))
      (node (ref "R27") (pin "1") (pinfunction "1_1") (pintype "passive"))
      (node (ref "R28") (pin "2") (pinfunction "2_2") (pintype "passive"))
      (node (ref "R30") (pin "2") (pinfunction "2_2") (pintype "passive"))
      (node (ref "R5") (pin "2") (pinfunction "2_2") (pintype "passive"))
      (node (ref "R6") (pin "1") (pinfunction "1_1") (pintype "passive"))
      (node (ref "R8") (pin "2") (pinfunction "2_2") (pintype "passive"))
      (node (ref "S1") (pin "2") (pinfunction "NO1_2") (pintype "passive"))
      (node (ref "S1") (pin "4") (pinfunction "NO2_4") (pintype "passive"))
      (node (ref "S2") (pin "2") (pinfunction "NO1_2") (pintype "passive"))
      (node (ref "S2") (pin "4") (pinfunction "NO2_4") (pintype "passive"))
      (node (ref "U1") (pin "1") (pinfunction "AGND_1") (pintype "passive"))
      (node (ref "U1") (pin "10") (pinfunction "SIM_GND_10") (pintype "passive"))
      (node (ref "U1") (pin "27") (pinfunction "GND_27") (pintype "passive"))
      (node (ref "U1") (pin "34") (pinfunction "GND_34") (pintype "passive"))
      (node (ref "U1") (pin "36") (pinfunction "GND_36") (pintype "passive"))
      (node (ref "U1") (pin "37") (pinfunction "GND_37") (pintype "passive"))
      (node (ref "U1") (pin "40") (pinfunction "GND_40") (pintype "passive"))
      (node (ref "U1") (pin "41") (pinfunction "GND_41") (pintype "passive"))
      (node (ref "U2") (pin "4") (pinfunction "GND_4") (pintype "passive"))
      (node (ref "U3") (pin "4") (pinfunction "GND_4") (pintype "passive"))
      (node (ref "U4") (pin "12") (pinfunction "VSSA/VREF-_12") (pintype "passive"))
      (node (ref "U4") (pin "18") (pinfunction "VSS_18") (pintype "passive"))
      (node (ref "U4") (pin "31") (pinfunction "VSS_31") (pintype "passive"))
      (node (ref "U4") (pin "47") (pinfunction "VSS_47") (pintype "passive"))
      (node (ref "U4") (pin "63") (pinfunction "VSS_63") (pintype "passive"))
      (node (ref "U5") (pin "3") (pinfunction "K_3") (pintype "passive"))
      (node (ref "U5") (pin "5") (pinfunction "GND_5") (pintype "passive"))
      (node (ref "U6") (pin "15") (pinfunction "GND_15") (pintype "power_in"))
      (node (ref "VR1") (pin "1") (pinfunction "GND_1") (pintype "passive"))
    )
    (net (code "54") (name "Net-(C9-Pad1)") (class "Default")
      (node (ref "C9") (pin "1") (pinfunction "1_1") (pintype "passive"))
      (node (ref "R5") (pin "1") (pinfunction "1_1") (pintype "passive"))
    )
    (net (code "55") (name "Net-(D1-PadK)") (class "Default")
      (node (ref "D1") (pin "K") (pinfunction "K_K") (pintype "passive"))
      (node (ref "R6") (pin "2") (pinfunction "2_2") (pintype "passive"))
    )
    (net (code "56") (name "Net-(D2-K)") (class "Default")
      (node (ref "C8") (pin "1") (pinfunction "1_1") (pintype "passive"))
      (node (ref "D2") (pin "2") (pinfunction "K_2") (pintype "passive"))
      (node (ref "L1") (pin "1") (pinfunction "1_1") (pintype "passive"))
      (node (ref "U2") (pin "3") (pinfunction "SW_3") (pintype "passive"))
    )
    (net (code "57") (name "Net-(D3-PadA)") (class "Default")
      (node (ref "D3") (pin "A") (pinfunction "A_A") (pintype "passive"))
      (node (ref "R13") (pin "1") (pinfunction "1_1") (pintype "passive"))
    )
    (net (code "58") (name "Net-(D4-A)") (class "Default")
      (node (ref "D4") (pin "1") (pinfunction "A_1") (pintype "passive"))
      (node (ref "K1") (pin "1") (pinfunction "1_1") (pintype "passive"))
      (node (ref "Q6") (pin "3") (pinfunction "C_3") (pintype "passive"))
    )
    (net (code "59") (name "Net-(D5-PadK)") (class "Default")
      (node (ref "D5") (pin "K") (pinfunction "K_K") (pintype "passive"))
      (node (ref "R16") (pin "2") (pinfunction "2_2") (pintype "passive"))
    )
    (net (code "60") (name "Net-(D6-PadK)") (class "Default")
      (node (ref "D6") (pin "K") (pinfunction "K_K") (pintype "passive"))
      (node (ref "R19") (pin "2") (pinfunction "2_2") (pintype "passive"))
    )
    (net (code "61") (name "Net-(D7-PadK)") (class "Default")
      (node (ref "D7") (pin "K") (pinfunction "K_K") (pintype "passive"))
      (node (ref "R22") (pin "1") (pinfunction "1_1") (pintype "passive"))
    )
    (net (code "62") (name "Net-(D8-PadK)") (class "Default")
      (node (ref "D8") (pin "K") (pinfunction "K_K") (pintype "passive"))
      (node (ref "R25") (pin "1") (pinfunction "1_1") (pintype "passive"))
    )
    (net (code "63") (name "Net-(D9-PadK)") (class "Default")
      (node (ref "D9") (pin "K") (pinfunction "K_K") (pintype "passive"))
      (node (ref "R29") (pin "1") (pinfunction "1_1") (pintype "passive"))
    )
    (net (code "64") (name "Net-(D10-A)") (class "Default")
      (node (ref "D10") (pin "1") (pinfunction "A_1") (pintype "passive"))
      (node (ref "P1") (pin "1") (pinfunction "1_1") (pintype "passive"))
    )
    (net (code "65") (name "Net-(K1-Pad3)") (class "Default")
      (node (ref "K1") (pin "3") (pinfunction "3_3") (pintype "passive"))
      (node (ref "P4") (pin "2") (pinfunction "2_2") (pintype "passive"))
    )
    (net (code "66") (name "Net-(P3-Pad2)") (class "Default")
      (node (ref "P3") (pin "2") (pinfunction "2_2") (pintype "passive"))
      (node (ref "R18") (pin "2") (pinfunction "2_2") (pintype "passive"))
    )
    (net (code "67") (name "Net-(P5-Pad7)") (class "Default")
      (node (ref "P5") (pin "7") (pinfunction "7_7") (pintype "passive"))
      (node (ref "R28") (pin "1") (pinfunction "1_1") (pintype "passive"))
    )
    (net (code "68") (name "Net-(Q1-D)") (class "Default")
      (node (ref "Q1") (pin "3") (pinfunction "D_3") (pintype "passive"))
      (node (ref "U1") (pin "42") (pinfunction "VBAT_42") (pintype "passive"))
      (node (ref "U1") (pin "43") (pinfunction "VBAT_43") (pintype "passive"))
    )
    (net (code "69") (name "Net-(Q2-B)") (class "Default")
      (node (ref "Q2") (pin "1") (pinfunction "B_1") (pintype "passive"))
      (node (ref "Q3") (pin "3") (pinfunction "C_3") (pintype "passive"))
      (node (ref "R2") (pin "1") (pinfunction "1_1") (pintype "passive"))
    )
    (net (code "70") (name "Net-(Q3-B)") (class "Default")
      (node (ref "Q3") (pin "1") (pinfunction "B_1") (pintype "passive"))
      (node (ref "R7") (pin "1") (pinfunction "1_1") (pintype "passive"))
    )
    (net (code "71") (name "Net-(Q4-B)") (class "Default")
      (node (ref "C12") (pin "1") (pinfunction "1_1") (pintype "passive"))
      (node (ref "Q4") (pin "1") (pinfunction "B_1") (pintype "passive"))
      (node (ref "R10") (pin "1") (pinfunction "1_1") (pintype "passive"))
    )
    (net (code "72") (name "Net-(Q5-B)") (class "Default")
      (node (ref "C14") (pin "2") (pinfunction "2_2") (pintype "passive"))
      (node (ref "Q5") (pin "1") (pinfunction "B_1") (pintype "passive"))
      (node (ref "R14") (pin "2") (pinfunction "2_2") (pintype "passive"))
    )
    (net (code "73") (name "Net-(Q6-B)") (class "Default")
      (node (ref "Q6") (pin "1") (pinfunction "B_1") (pintype "passive"))
      (node (ref "R20") (pin "2") (pinfunction "2_2") (pintype "passive"))
    )
    (net (code "74") (name "Net-(U1-NETLIGHT)") (class "Default")
      (node (ref "R13") (pin "2") (pinfunction "2_2") (pintype "passive"))
      (node (ref "U1") (pin "16") (pinfunction "NETLIGHT_16") (pintype "passive"))
    )
    (net (code "75") (name "Net-(U1-RF_ANT)") (class "Default")
      (node (ref "J1") (pin "1") (pinfunction "1_1") (pintype "passive"))
      (node (ref "U1") (pin "35") (pinfunction "RF_ANT_35") (pintype "passive"))
    )
    (net (code "76") (name "Net-(U2-BS)") (class "Default")
      (node (ref "C8") (pin "2") (pinfunction "2_2") (pintype "passive"))
      (node (ref "U2") (pin "1") (pinfunction "BS_1") (pintype "passive"))
    )
    (net (code "77") (name "Net-(U2-COMP)") (class "Default")
      (node (ref "C9") (pin "2") (pinfunction "2_2") (pintype "passive"))
      (node (ref "U2") (pin "6") (pinfunction "COMP_6") (pintype "passive"))
    )
    (net (code "78") (name "Net-(U2-EN)") (class "Default")
      (node (ref "R3") (pin "2") (pinfunction "2_2") (pintype "passive"))
      (node (ref "U2") (pin "7") (pinfunction "EN_7") (pintype "passive"))
    )
    (net (code "79") (name "Net-(U2-FB)") (class "Default")
      (node (ref "R8") (pin "1") (pinfunction "1_1") (pintype "passive"))
      (node (ref "R9") (pin "1") (pinfunction "1_1") (pintype "passive"))
      (node (ref "U2") (pin "5") (pinfunction "FB_5") (pintype "passive"))
    )
    (net (code "80") (name "Net-(U2-SS)") (class "Default")
      (node (ref "C7") (pin "2") (pinfunction "2_2") (pintype "passive"))
      (node (ref "U2") (pin "8") (pinfunction "SS_8") (pintype "passive"))
    )
    (net (code "81") (name "Net-(U4-OSC_IN)") (class "Default")
      (node (ref "C18") (pin "2") (pinfunction "2_2") (pintype "passive"))
      (node (ref "U4") (pin "5") (pinfunction "OSC_IN_5") (pintype "passive"))
      (node (ref "Y1") (pin "1") (pinfunction "OSC1_1") (pintype "passive"))
    )
    (net (code "82") (name "Net-(U4-OSC_OUT)") (class "Default")
      (node (ref "C19") (pin "1") (pinfunction "1_1") (pintype "passive"))
      (node (ref "U4") (pin "6") (pinfunction "OSC_OUT_6") (pintype "passive"))
      (node (ref "Y1") (pin "2") (pinfunction "OSC2_2") (pintype "passive"))
    )
    (net (code "83") (name "Net-(U4-PC14)") (class "Default")
      (node (ref "C38") (pin "2") (pinfunction "2_2") (pintype "passive"))
      (node (ref "U4") (pin "3") (pinfunction "PC14_3") (pintype "passive"))
      (node (ref "Y2") (pin "2") (pinfunction "OSC2_2") (pintype "passive"))
    )
    (net (code "84") (name "Net-(U4-PC15)") (class "Default")
      (node (ref "C37") (pin "1") (pinfunction "1_1") (pintype "passive"))
      (node (ref "U4") (pin "4") (pinfunction "PC15_4") (pintype "passive"))
      (node (ref "Y2") (pin "1") (pinfunction "OSC1_1") (pintype "passive"))
    )
    (net (code "85") (name "Net-(U4-VCAP_1)") (class "Default")
      (node (ref "C24") (pin "1") (pinfunction "1_1") (pintype "passive"))
      (node (ref "U4") (pin "30") (pinfunction "VCAP_1_30") (pintype "passive"))
    )
    (net (code "86") (name "Net-(U5-A)") (class "Default")
      (node (ref "R18") (pin "1") (pinfunction "1_1") (pintype "passive"))
      (node (ref "U5") (pin "2") (pinfunction "A_2") (pintype "passive"))
    )
    (net (code "87") (name "Net-(U6-C1+)") (class "Default")
      (node (ref "C32") (pin "2") (pinfunction "2_2") (pintype "passive"))
      (node (ref "U6") (pin "1") (pinfunction "C1+_1") (pintype "passive"))
    )
    (net (code "88") (name "Net-(U6-C1-)") (class "Default")
      (node (ref "C32") (pin "1") (pinfunction "1_1") (pintype "passive"))
      (node (ref "U6") (pin "3") (pinfunction "C1-_3") (pintype "passive"))
    )
    (net (code "89") (name "Net-(U6-C2+)") (class "Default")
      (node (ref "C34") (pin "1") (pinfunction "1_1") (pintype "passive"))
      (node (ref "U6") (pin "4") (pinfunction "C2+_4") (pintype "passive"))
    )
    (net (code "90") (name "Net-(U6-C2-)") (class "Default")
      (node (ref "C34") (pin "2") (pinfunction "2_2") (pintype "passive"))
      (node (ref "U6") (pin "5") (pinfunction "C2-_5") (pintype "passive"))
    )
    (net (code "91") (name "Net-(U6-VDD)") (class "Default")
      (node (ref "C33") (pin "1") (pinfunction "1_1") (pintype "passive"))
      (node (ref "U6") (pin "2") (pinfunction "VDD_2") (pintype "power_in"))
    )
    (net (code "92") (name "Net-(U6-VEE)") (class "Default")
      (node (ref "C36") (pin "1") (pinfunction "1_1") (pintype "passive"))
      (node (ref "U6") (pin "6") (pinfunction "VEE_6") (pintype "power_in"))
    )
    (net (code "93") (name "Net-(VR1-Vin)") (class "Default")
      (node (ref "C2") (pin "2") (pinfunction "2_2") (pintype "passive"))
      (node (ref "R31") (pin "2") (pinfunction "2_2") (pintype "passive"))
      (node (ref "VR1") (pin "3") (pinfunction "Vin_3") (pintype "passive"))
    )
    (net (code "94") (name "VDD_EXT") (class "Default")
      (node (ref "C12") (pin "2") (pinfunction "2_2") (pintype "passive"))
      (node (ref "C13") (pin "2") (pinfunction "2_2") (pintype "passive"))
      (node (ref "C14") (pin "1") (pinfunction "1_1") (pintype "passive"))
      (node (ref "R10") (pin "2") (pinfunction "2_2") (pintype "passive"))
      (node (ref "R11") (pin "2") (pinfunction "2_2") (pintype "passive"))
      (node (ref "R14") (pin "1") (pinfunction "1_1") (pintype "passive"))
      (node (ref "R7") (pin "2") (pinfunction "2_2") (pintype "passive"))
      (node (ref "U1") (pin "24") (pinfunction "VDD_EXT_24") (pintype "passive"))
    )
    (net (code "95") (name "unconnected-(U1-ADC0-Pad9)") (class "Default")
      (node (ref "U1") (pin "9") (pinfunction "ADC0_9") (pintype "passive"))
    )
    (net (code "96") (name "unconnected-(U1-AVDD-Pad8)") (class "Default")
      (node (ref "U1") (pin "8") (pinfunction "AVDD_8") (pintype "passive"))
    )
    (net (code "97") (name "unconnected-(U1-BT_ANT-Pad26)") (class "Default")
      (node (ref "U1") (pin "26") (pinfunction "BT_ANT_26") (pintype "passive"))
    )
    (net (code "98") (name "unconnected-(U1-CTS-Pad22)") (class "Default")
      (node (ref "U1") (pin "22") (pinfunction "CTS_22") (pintype "passive"))
    )
    (net (code "99") (name "unconnected-(U1-DBG_RXD-Pad38)") (class "Default")
      (node (ref "U1") (pin "38") (pinfunction "DBG_RXD_38") (pintype "passive"))
    )
    (net (code "100") (name "unconnected-(U1-DBG_TXD-Pad39)") (class "Default")
      (node (ref "U1") (pin "39") (pinfunction "DBG_TXD_39") (pintype "passive"))
    )
    (net (code "101") (name "unconnected-(U1-DCD-Pad21)") (class "Default")
      (node (ref "U1") (pin "21") (pinfunction "DCD_21") (pintype "passive"))
    )
    (net (code "102") (name "unconnected-(U1-MICN-Pad4)") (class "Default")
      (node (ref "U1") (pin "4") (pinfunction "MICN_4") (pintype "passive"))
    )
    (net (code "103") (name "unconnected-(U1-MICP-Pad3)") (class "Default")
      (node (ref "U1") (pin "3") (pinfunction "MICP_3") (pintype "passive"))
    )
    (net (code "104") (name "unconnected-(U1-PCM_CLK-Pad30)") (class "Default")
      (node (ref "U1") (pin "30") (pinfunction "PCM_CLK_30") (pintype "passive"))
    )
    (net (code "105") (name "unconnected-(U1-PCM_IN-Pad32)") (class "Default")
      (node (ref "U1") (pin "32") (pinfunction "PCM_IN_32") (pintype "passive"))
    )
    (net (code "106") (name "unconnected-(U1-PCM_OUT-Pad33)") (class "Default")
      (node (ref "U1") (pin "33") (pinfunction "PCM_OUT_33") (pintype "passive"))
    )
    (net (code "107") (name "unconnected-(U1-PCM_SYNC-Pad31)") (class "Default")
      (node (ref "U1") (pin "31") (pinfunction "PCM_SYNC_31") (pintype "passive"))
    )
    (net (code "108") (name "unconnected-(U1-RFTXMON-Pad25)") (class "Default")
      (node (ref "U1") (pin "25") (pinfunction "RFTXMON_25") (pintype "passive"))
    )
    (net (code "109") (name "unconnected-(U1-RI-Pad20)") (class "Default")
      (node (ref "U1") (pin "20") (pinfunction "RI_20") (pintype "passive"))
    )
    (net (code "110") (name "unconnected-(U1-RTS-Pad23)") (class "Default")
      (node (ref "U1") (pin "23") (pinfunction "RTS_23") (pintype "passive"))
    )
    (net (code "111") (name "unconnected-(U1-RXD_AUX-Pad28)") (class "Default")
      (node (ref "U1") (pin "28") (pinfunction "RXD_AUX_28") (pintype "passive"))
    )
    (net (code "112") (name "unconnected-(U1-SPK1N-Pad6)") (class "Default")
      (node (ref "U1") (pin "6") (pinfunction "SPK1N_6") (pintype "passive"))
    )
    (net (code "113") (name "unconnected-(U1-SPK1P-Pad5)") (class "Default")
      (node (ref "U1") (pin "5") (pinfunction "SPK1P_5") (pintype "passive"))
    )
    (net (code "114") (name "unconnected-(U1-SPK2P-Pad2)") (class "Default")
      (node (ref "U1") (pin "2") (pinfunction "SPK2P_2") (pintype "passive"))
    )
    (net (code "115") (name "unconnected-(U1-TXD_AUX-Pad29)") (class "Default")
      (node (ref "U1") (pin "29") (pinfunction "TXD_AUX_29") (pintype "passive"))
    )
    (net (code "116") (name "unconnected-(U1-VRTC-Pad44)") (class "Default")
      (node (ref "U1") (pin "44") (pinfunction "VRTC_44") (pintype "passive"))
    )
    (net (code "117") (name "unconnected-(U4-PA11-Pad44)") (class "Default")
      (node (ref "U4") (pin "44") (pinfunction "PA11_44") (pintype "passive"))
    )
    (net (code "118") (name "unconnected-(U4-PA15-Pad50)") (class "Default")
      (node (ref "U4") (pin "50") (pinfunction "PA15_50") (pintype "passive"))
    )
    (net (code "119") (name "unconnected-(U4-PB3-Pad55)") (class "Default")
      (node (ref "U4") (pin "55") (pinfunction "PB3_55") (pintype "passive"))
    )
    (net (code "120") (name "unconnected-(U4-PB4-Pad56)") (class "Default")
      (node (ref "U4") (pin "56") (pinfunction "PB4_56") (pintype "passive"))
    )
    (net (code "121") (name "unconnected-(U4-PB5-Pad57)") (class "Default")
      (node (ref "U4") (pin "57") (pinfunction "PB5_57") (pintype "passive"))
    )
    (net (code "122") (name "unconnected-(U4-PB6-Pad58)") (class "Default")
      (node (ref "U4") (pin "58") (pinfunction "PB6_58") (pintype "passive"))
    )
    (net (code "123") (name "unconnected-(U4-PB7-Pad59)") (class "Default")
      (node (ref "U4") (pin "59") (pinfunction "PB7_59") (pintype "passive"))
    )
    (net (code "124") (name "unconnected-(U4-PB8-Pad61)") (class "Default")
      (node (ref "U4") (pin "61") (pinfunction "PB8_61") (pintype "passive"))
    )
    (net (code "125") (name "unconnected-(U4-PB9-Pad62)") (class "Default")
      (node (ref "U4") (pin "62") (pinfunction "PB9_62") (pintype "passive"))
    )
    (net (code "126") (name "unconnected-(U4-PB10-Pad29)") (class "Default")
      (node (ref "U4") (pin "29") (pinfunction "PB10_29") (pintype "passive"))
    )
    (net (code "127") (name "unconnected-(U4-PC1-Pad9)") (class "Default")
      (node (ref "U4") (pin "9") (pinfunction "PC1_9") (pintype "passive"))
    )
    (net (code "128") (name "unconnected-(U4-PC10-Pad51)") (class "Default")
      (node (ref "U4") (pin "51") (pinfunction "PC10_51") (pintype "passive"))
    )
    (net (code "129") (name "unconnected-(U4-PC11-Pad52)") (class "Default")
      (node (ref "U4") (pin "52") (pinfunction "PC11_52") (pintype "passive"))
    )
    (net (code "130") (name "unconnected-(U4-PC12-Pad53)") (class "Default")
      (node (ref "U4") (pin "53") (pinfunction "PC12_53") (pintype "passive"))
    )
    (net (code "131") (name "unconnected-(U4-PD2-Pad54)") (class "Default")
      (node (ref "U4") (pin "54") (pinfunction "PD2_54") (pintype "passive"))
    )
    (net (code "132") (name "unconnected-(U5-NC-Pad1)") (class "Default")
      (node (ref "U5") (pin "1") (pinfunction "NC_1") (pintype "passive"))
    )
    (net (code "133") (name "unconnected-(U5-NC-Pad4)") (class "Default")
      (node (ref "U5") (pin "4") (pinfunction "NC_4") (pintype "passive"))
    )
    (net (code "134") (name "unconnected-(U5-VE-Pad7)") (class "Default")
      (node (ref "U5") (pin "7") (pinfunction "VE_7") (pintype "passive"))
    )
  )
)
